# Moodlight20_ETP2.net
KiCad netlist of a schematic drawn in EAGLE
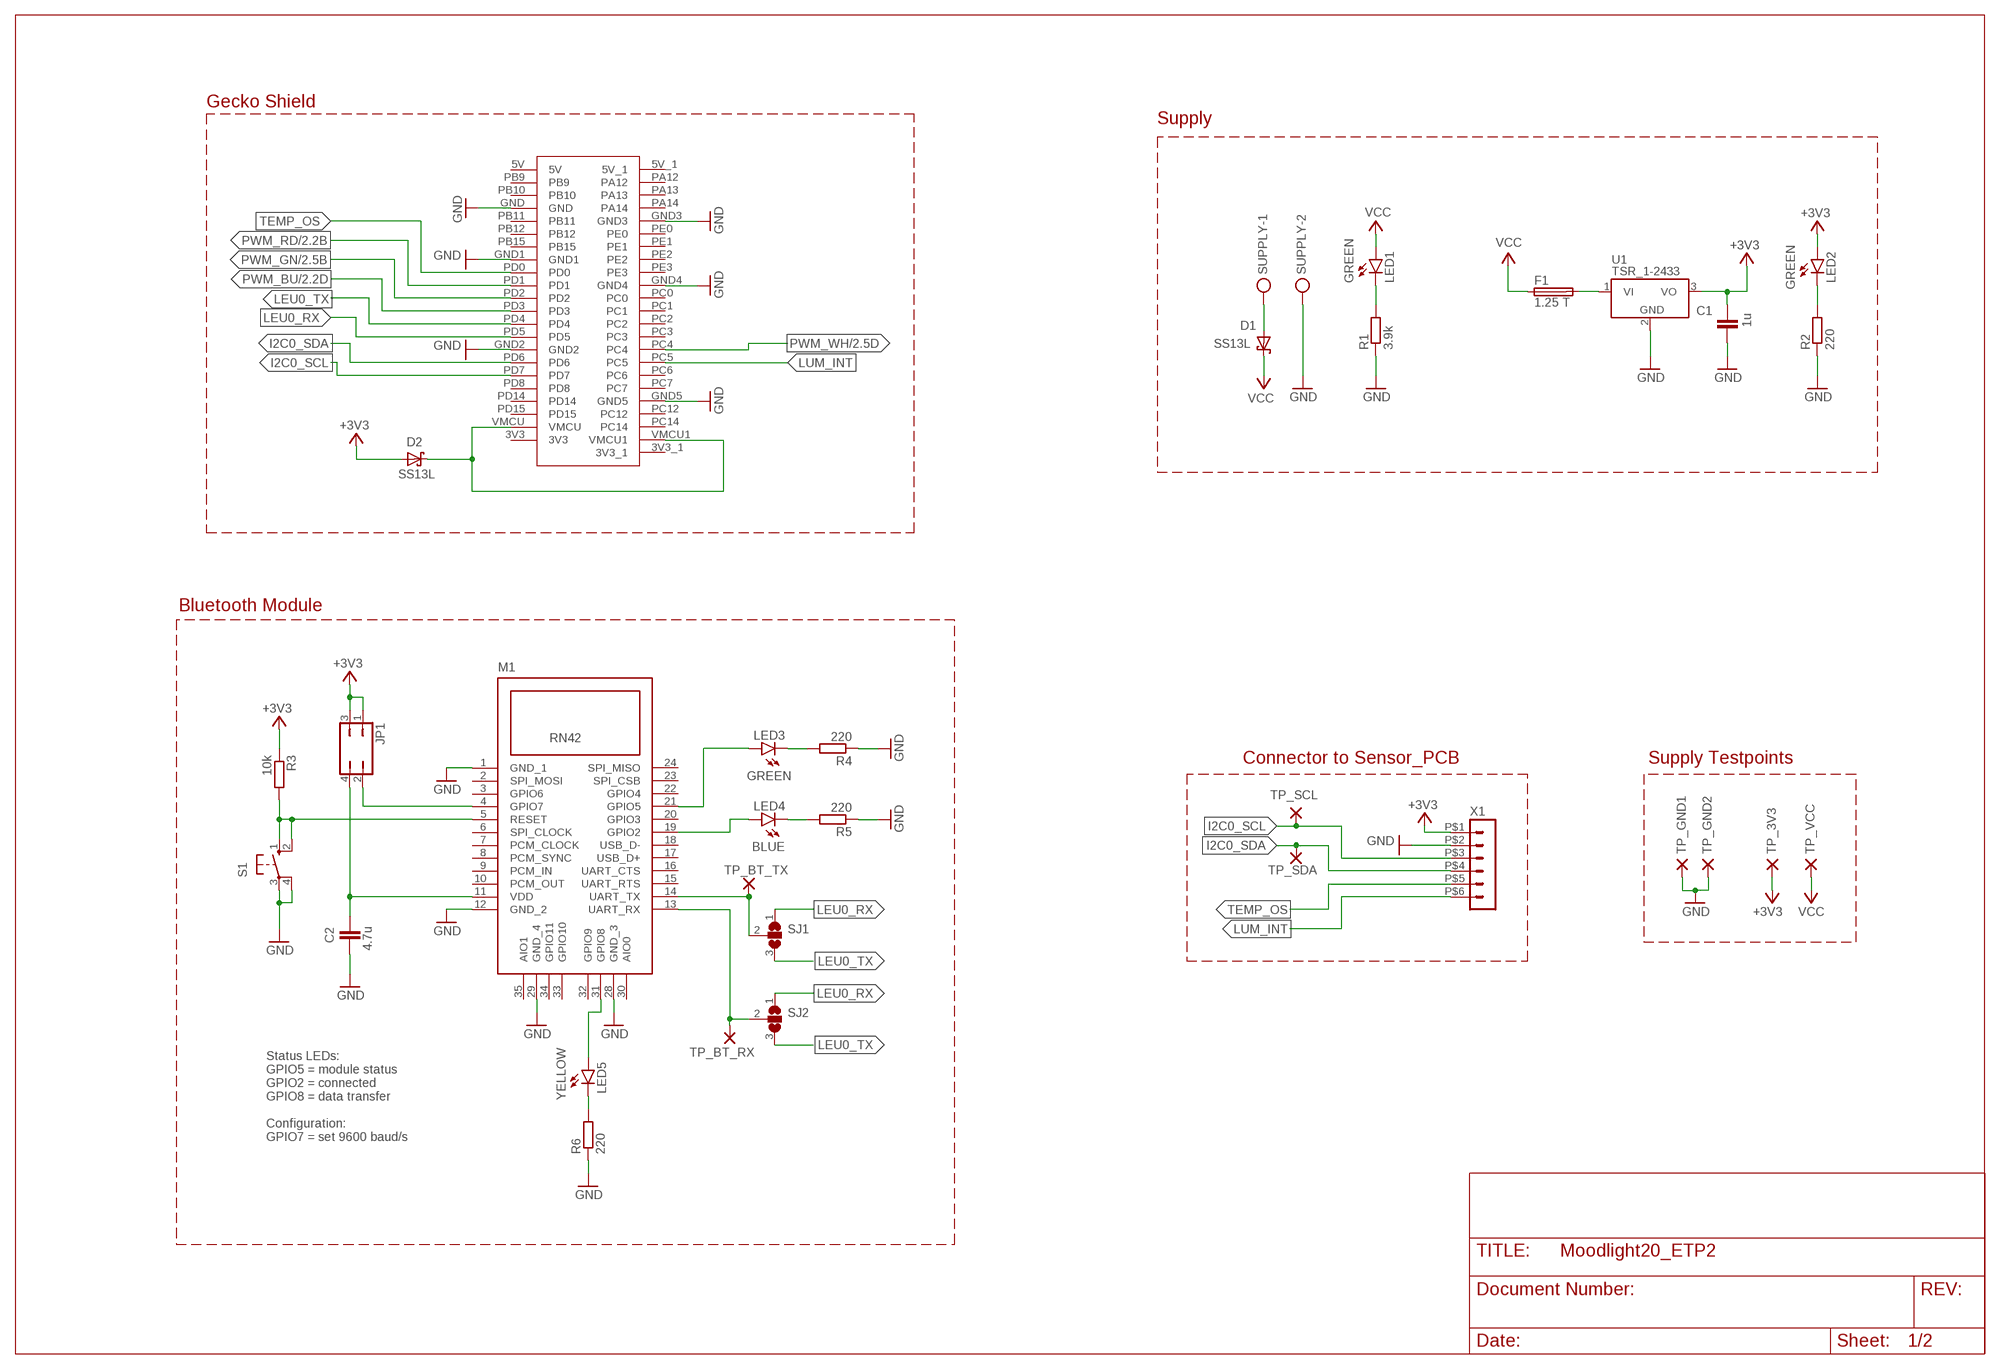
[diagram p0: schematic, sheet 1]
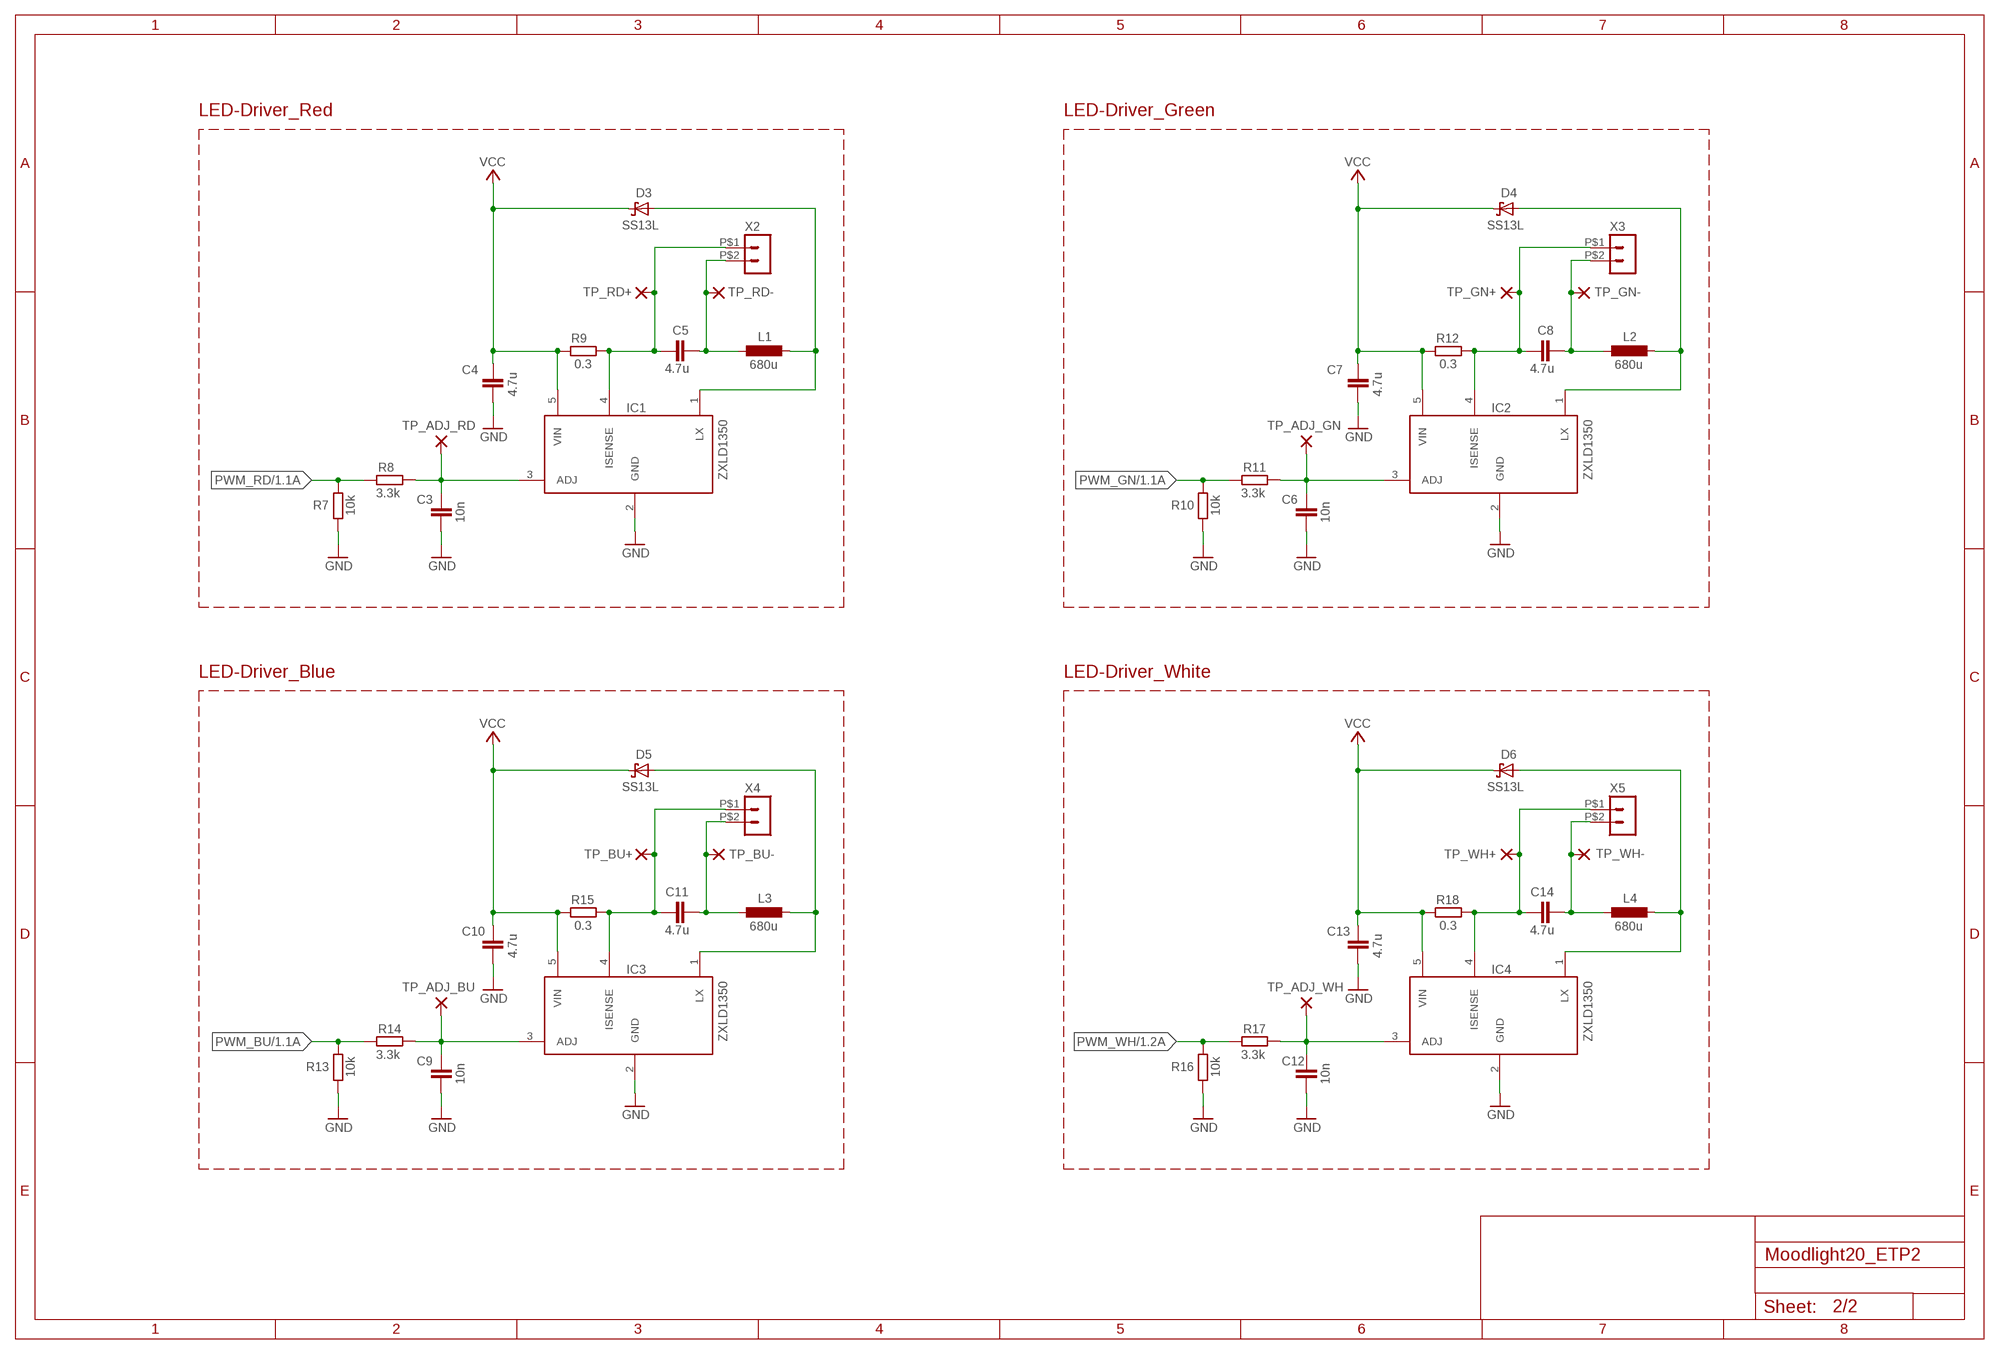
[diagram p1: schematic, sheet 2]

(export (version "E")
  (design (tool "Eeschema 10.0.6"))
  (components
    (comp (ref "C1")
      (value "1u")
      (footprint "eagle-import:C0805K")
      (libsource (lib "eagle-import") (part "C-EUC0805K"))
    )
    (comp (ref "C2")
      (value "4.7u")
      (footprint "eagle-import:C0805K")
      (libsource (lib "eagle-import") (part "C-EUC0805K"))
    )
    (comp (ref "D1")
      (value "SS13L")
      (footprint "eagle-import:SUB-SMA")
      (libsource (lib "eagle-import") (part "SS13L"))
    )
    (comp (ref "D2")
      (value "SS13L")
      (footprint "eagle-import:SUB-SMA")
      (libsource (lib "eagle-import") (part "SS13L"))
    )
    (comp (ref "F1")
      (value "1.25 T")
      (footprint "eagle-import:19560")
      (fields (field (name "MPN") "56000001009"))
      (libsource (lib "eagle-import") (part "19560"))
    )
    (comp (ref "GECKO")
      (value "GECKO_SHIELD")
      (footprint "eagle-import:GECKO_SHIELD")
      (libsource (lib "eagle-import") (part "GECKO_SHIELD"))
    )
    (comp (ref "JP1")
      (value "JP2Q")
      (footprint "eagle-import:JP2Q")
      (libsource (lib "eagle-import") (part "JP2Q"))
    )
    (comp (ref "LED1")
      (value "GREEN")
      (footprint "eagle-import:CHIP-LED0805")
      (fields (field (name "SPICEPREFIX") "L"))
      (libsource (lib "eagle-import") (part "LEDCHIP-LED0805"))
    )
    (comp (ref "LED2")
      (value "GREEN")
      (footprint "eagle-import:CHIP-LED0805")
      (fields (field (name "SPICEPREFIX") "L"))
      (libsource (lib "eagle-import") (part "LEDCHIP-LED0805"))
    )
    (comp (ref "LED3")
      (value "GREEN")
      (footprint "eagle-import:CHIP-LED0805")
      (fields (field (name "SPICEPREFIX") "L"))
      (libsource (lib "eagle-import") (part "LEDCHIP-LED0805"))
    )
    (comp (ref "LED4")
      (value "BLUE")
      (footprint "eagle-import:CHIP-LED0805")
      (fields (field (name "SPICEPREFIX") "L"))
      (libsource (lib "eagle-import") (part "LEDCHIP-LED0805"))
    )
    (comp (ref "LED5")
      (value "YELLOW")
      (footprint "eagle-import:CHIP-LED0805")
      (fields (field (name "SPICEPREFIX") "L"))
      (libsource (lib "eagle-import") (part "LEDCHIP-LED0805"))
    )
    (comp (ref "M1")
      (value "RN42_BLUETOOTH")
      (footprint "eagle-import:RN42_BLUETOOTH")
      (libsource (lib "eagle-import") (part "RN42_BLUETOOTH"))
    )
    (comp (ref "R1")
      (value "3.9k")
      (footprint "eagle-import:R0805")
      (libsource (lib "eagle-import") (part "R-EU_R0805"))
    )
    (comp (ref "R2")
      (value "220")
      (footprint "eagle-import:R0805")
      (libsource (lib "eagle-import") (part "R-EU_R0805"))
    )
    (comp (ref "R3")
      (value "10k")
      (footprint "eagle-import:R0805")
      (libsource (lib "eagle-import") (part "R-EU_R0805"))
    )
    (comp (ref "R4")
      (value "220")
      (footprint "eagle-import:R0805")
      (libsource (lib "eagle-import") (part "R-EU_R0805"))
    )
    (comp (ref "R5")
      (value "220")
      (footprint "eagle-import:R0805")
      (libsource (lib "eagle-import") (part "R-EU_R0805"))
    )
    (comp (ref "R6")
      (value "220")
      (footprint "eagle-import:R0805")
      (libsource (lib "eagle-import") (part "R-EU_R0805"))
    )
    (comp (ref "S1")
      (value "10-XX")
      (footprint "eagle-import:B3F-10XX")
      (fields (field (name "MPN") "B3F-1000"))
      (libsource (lib "eagle-import") (part "10-XX"))
    )
    (comp (ref "SJ1")
      (value "SJ2W")
      (footprint "eagle-import:SJ_2")
      (libsource (lib "eagle-import") (part "SJ2W"))
    )
    (comp (ref "SJ2")
      (value "SJ2W")
      (footprint "eagle-import:SJ_2")
      (libsource (lib "eagle-import") (part "SJ2W"))
    )
    (comp (ref "SUPPLY")
      (value "MKDSN1,5/2-5,08")
      (footprint "eagle-import:MKDSN1,5_2-5,08")
      (libsource (lib "eagle-import") (part "MKDSN1,5/2-5,08"))
    )
    (comp (ref "TP_3V3")
      (value "TESTPOINT")
      (footprint "eagle-import:3,2_1,6")
      (libsource (lib "eagle-import") (part "TESTPOINT"))
    )
    (comp (ref "TP_BT_RX")
      (value "TESTPOINT")
      (footprint "eagle-import:3,2_1,6")
      (libsource (lib "eagle-import") (part "TESTPOINT"))
    )
    (comp (ref "TP_BT_TX")
      (value "TESTPOINT")
      (footprint "eagle-import:3,2_1,6")
      (libsource (lib "eagle-import") (part "TESTPOINT"))
    )
    (comp (ref "TP_GND1")
      (value "TESTPOINT")
      (footprint "eagle-import:3,2_1,6")
      (libsource (lib "eagle-import") (part "TESTPOINT"))
    )
    (comp (ref "TP_GND2")
      (value "TESTPOINT")
      (footprint "eagle-import:3,2_1,6")
      (libsource (lib "eagle-import") (part "TESTPOINT"))
    )
    (comp (ref "TP_SCL")
      (value "TESTPOINT")
      (footprint "eagle-import:3,2_1,6")
      (libsource (lib "eagle-import") (part "TESTPOINT"))
    )
    (comp (ref "TP_SDA")
      (value "TESTPOINT")
      (footprint "eagle-import:3,2_1,6")
      (libsource (lib "eagle-import") (part "TESTPOINT"))
    )
    (comp (ref "TP_VCC")
      (value "TESTPOINT")
      (footprint "eagle-import:3,2_1,6")
      (libsource (lib "eagle-import") (part "TESTPOINT"))
    )
    (comp (ref "U1")
      (value "TSR_1-2433")
      (footprint "eagle-import:TSR-1")
      (libsource (lib "eagle-import") (part "TSR_1-2433"))
    )
    (comp (ref "X1")
      (value "HEADER_POS6_43045-0612")
      (footprint "eagle-import:43045-0612")
      (libsource (lib "eagle-import") (part "HEADER_POS6_?43045-0612"))
    )
    (comp (ref "C3")
      (value "10n")
      (footprint "eagle-import:C0805K")
      (libsource (lib "eagle-import") (part "C-EUC0805K"))
    )
    (comp (ref "C4")
      (value "4.7u")
      (footprint "eagle-import:C0805K")
      (libsource (lib "eagle-import") (part "C-EUC0805K"))
    )
    (comp (ref "C5")
      (value "4.7u")
      (footprint "eagle-import:C0805K")
      (libsource (lib "eagle-import") (part "C-EUC0805K"))
    )
    (comp (ref "C6")
      (value "10n")
      (footprint "eagle-import:C0805K")
      (libsource (lib "eagle-import") (part "C-EUC0805K"))
    )
    (comp (ref "C7")
      (value "4.7u")
      (footprint "eagle-import:C0805K")
      (libsource (lib "eagle-import") (part "C-EUC0805K"))
    )
    (comp (ref "C8")
      (value "4.7u")
      (footprint "eagle-import:C0805K")
      (libsource (lib "eagle-import") (part "C-EUC0805K"))
    )
    (comp (ref "C9")
      (value "10n")
      (footprint "eagle-import:C0805K")
      (libsource (lib "eagle-import") (part "C-EUC0805K"))
    )
    (comp (ref "C10")
      (value "4.7u")
      (footprint "eagle-import:C0805K")
      (libsource (lib "eagle-import") (part "C-EUC0805K"))
    )
    (comp (ref "C11")
      (value "4.7u")
      (footprint "eagle-import:C0805K")
      (libsource (lib "eagle-import") (part "C-EUC0805K"))
    )
    (comp (ref "C12")
      (value "10n")
      (footprint "eagle-import:C0805K")
      (libsource (lib "eagle-import") (part "C-EUC0805K"))
    )
    (comp (ref "C13")
      (value "4.7u")
      (footprint "eagle-import:C0805K")
      (libsource (lib "eagle-import") (part "C-EUC0805K"))
    )
    (comp (ref "C14")
      (value "4.7u")
      (footprint "eagle-import:C0805K")
      (libsource (lib "eagle-import") (part "C-EUC0805K"))
    )
    (comp (ref "D3")
      (value "SS13L")
      (footprint "eagle-import:SUB-SMA")
      (libsource (lib "eagle-import") (part "SS13L"))
    )
    (comp (ref "D4")
      (value "SS13L")
      (footprint "eagle-import:SUB-SMA")
      (libsource (lib "eagle-import") (part "SS13L"))
    )
    (comp (ref "D5")
      (value "SS13L")
      (footprint "eagle-import:SUB-SMA")
      (libsource (lib "eagle-import") (part "SS13L"))
    )
    (comp (ref "D6")
      (value "SS13L")
      (footprint "eagle-import:SUB-SMA")
      (libsource (lib "eagle-import") (part "SS13L"))
    )
    (comp (ref "IC1")
      (value "ZXLD1350")
      (footprint "eagle-import:TSOT23-5L")
      (libsource (lib "eagle-import") (part "ZXLD1350"))
    )
    (comp (ref "IC2")
      (value "ZXLD1350")
      (footprint "eagle-import:TSOT23-5L")
      (libsource (lib "eagle-import") (part "ZXLD1350"))
    )
    (comp (ref "IC3")
      (value "ZXLD1350")
      (footprint "eagle-import:TSOT23-5L")
      (libsource (lib "eagle-import") (part "ZXLD1350"))
    )
    (comp (ref "IC4")
      (value "ZXLD1350")
      (footprint "eagle-import:TSOT23-5L")
      (libsource (lib "eagle-import") (part "ZXLD1350"))
    )
    (comp (ref "L1")
      (value "680u")
      (footprint "eagle-import:POWER-CHOKE_WE-PD")
      (libsource (lib "eagle-import") (part "POWER-CHOKE_WE-PD"))
    )
    (comp (ref "L2")
      (value "680u")
      (footprint "eagle-import:POWER-CHOKE_WE-PD")
      (libsource (lib "eagle-import") (part "POWER-CHOKE_WE-PD"))
    )
    (comp (ref "L3")
      (value "680u")
      (footprint "eagle-import:POWER-CHOKE_WE-PD")
      (libsource (lib "eagle-import") (part "POWER-CHOKE_WE-PD"))
    )
    (comp (ref "L4")
      (value "680u")
      (footprint "eagle-import:POWER-CHOKE_WE-PD")
      (libsource (lib "eagle-import") (part "POWER-CHOKE_WE-PD"))
    )
    (comp (ref "R7")
      (value "10k")
      (footprint "eagle-import:R0805")
      (libsource (lib "eagle-import") (part "R-EU_R0805"))
    )
    (comp (ref "R8")
      (value "3.3k")
      (footprint "eagle-import:R0805")
      (libsource (lib "eagle-import") (part "R-EU_R0805"))
    )
    (comp (ref "R9")
      (value "0.3")
      (footprint "eagle-import:R1206")
      (libsource (lib "eagle-import") (part "R-EU_R1206"))
    )
    (comp (ref "R10")
      (value "10k")
      (footprint "eagle-import:R0805")
      (libsource (lib "eagle-import") (part "R-EU_R0805"))
    )
    (comp (ref "R11")
      (value "3.3k")
      (footprint "eagle-import:R0805")
      (libsource (lib "eagle-import") (part "R-EU_R0805"))
    )
    (comp (ref "R12")
      (value "0.3")
      (footprint "eagle-import:R1206")
      (libsource (lib "eagle-import") (part "R-EU_R1206"))
    )
    (comp (ref "R13")
      (value "10k")
      (footprint "eagle-import:R0805")
      (libsource (lib "eagle-import") (part "R-EU_R0805"))
    )
    (comp (ref "R14")
      (value "3.3k")
      (footprint "eagle-import:R0805")
      (libsource (lib "eagle-import") (part "R-EU_R0805"))
    )
    (comp (ref "R15")
      (value "0.3")
      (footprint "eagle-import:R1206")
      (libsource (lib "eagle-import") (part "R-EU_R1206"))
    )
    (comp (ref "R16")
      (value "10k")
      (footprint "eagle-import:R0805")
      (libsource (lib "eagle-import") (part "R-EU_R0805"))
    )
    (comp (ref "R17")
      (value "3.3k")
      (footprint "eagle-import:R0805")
      (libsource (lib "eagle-import") (part "R-EU_R0805"))
    )
    (comp (ref "R18")
      (value "0.3")
      (footprint "eagle-import:R1206")
      (libsource (lib "eagle-import") (part "R-EU_R1206"))
    )
    (comp (ref "TP_ADJ_BU")
      (value "TESTPOINT")
      (footprint "eagle-import:3,2_1,6")
      (libsource (lib "eagle-import") (part "TESTPOINT"))
    )
    (comp (ref "TP_ADJ_GN")
      (value "TESTPOINT")
      (footprint "eagle-import:3,2_1,6")
      (libsource (lib "eagle-import") (part "TESTPOINT"))
    )
    (comp (ref "TP_ADJ_RD")
      (value "TESTPOINT")
      (footprint "eagle-import:3,2_1,6")
      (libsource (lib "eagle-import") (part "TESTPOINT"))
    )
    (comp (ref "TP_ADJ_WH")
      (value "TESTPOINT")
      (footprint "eagle-import:3,2_1,6")
      (libsource (lib "eagle-import") (part "TESTPOINT"))
    )
    (comp (ref "TP_BU+")
      (value "TESTPOINT")
      (footprint "eagle-import:3,2_1,6")
      (libsource (lib "eagle-import") (part "TESTPOINT"))
    )
    (comp (ref "TP_BU-")
      (value "TESTPOINT")
      (footprint "eagle-import:3,2_1,6")
      (libsource (lib "eagle-import") (part "TESTPOINT"))
    )
    (comp (ref "TP_GN+")
      (value "TESTPOINT")
      (footprint "eagle-import:3,2_1,6")
      (libsource (lib "eagle-import") (part "TESTPOINT"))
    )
    (comp (ref "TP_GN-")
      (value "TESTPOINT")
      (footprint "eagle-import:3,2_1,6")
      (libsource (lib "eagle-import") (part "TESTPOINT"))
    )
    (comp (ref "TP_RD+")
      (value "TESTPOINT")
      (footprint "eagle-import:3,2_1,6")
      (libsource (lib "eagle-import") (part "TESTPOINT"))
    )
    (comp (ref "TP_RD-")
      (value "TESTPOINT")
      (footprint "eagle-import:3,2_1,6")
      (libsource (lib "eagle-import") (part "TESTPOINT"))
    )
    (comp (ref "TP_WH+")
      (value "TESTPOINT")
      (footprint "eagle-import:3,2_1,6")
      (libsource (lib "eagle-import") (part "TESTPOINT"))
    )
    (comp (ref "TP_WH-")
      (value "TESTPOINT")
      (footprint "eagle-import:3,2_1,6")
      (libsource (lib "eagle-import") (part "TESTPOINT"))
    )
    (comp (ref "X2")
      (value "HEADER_POS2_43650-0215")
      (footprint "eagle-import:43650-0215")
      (libsource (lib "eagle-import") (part "HEADER_POS2_?43650-0215"))
    )
    (comp (ref "X3")
      (value "HEADER_POS2_43650-0215")
      (footprint "eagle-import:43650-0215")
      (libsource (lib "eagle-import") (part "HEADER_POS2_?43650-0215"))
    )
    (comp (ref "X4")
      (value "HEADER_POS2_43650-0215")
      (footprint "eagle-import:43650-0215")
      (libsource (lib "eagle-import") (part "HEADER_POS2_?43650-0215"))
    )
    (comp (ref "X5")
      (value "HEADER_POS2_43650-0215")
      (footprint "eagle-import:43650-0215")
      (libsource (lib "eagle-import") (part "HEADER_POS2_?43650-0215"))
    )
  )
  (nets
    (net (code "1") (name "+3V3") (class "Default")
      (node (ref "C1") (pin "1") (pinfunction "1_1") (pintype "passive"))
      (node (ref "D2") (pin "A") (pinfunction "A_A") (pintype "passive"))
      (node (ref "JP1") (pin "1") (pinfunction "1_1") (pintype "passive"))
      (node (ref "JP1") (pin "3") (pinfunction "3_3") (pintype "passive"))
      (node (ref "LED2") (pin "A") (pinfunction "A_A") (pintype "passive"))
      (node (ref "R3") (pin "1") (pinfunction "1_1") (pintype "passive"))
      (node (ref "TP_3V3") (pin "1") (pinfunction "P_1") (pintype "passive"))
      (node (ref "U1") (pin "3") (pinfunction "VO_3") (pintype "power_in"))
      (node (ref "X1") (pin "P$1") (pinfunction "1_P$1") (pintype "passive"))
    )
    (net (code "2") (name "GND") (class "Default")
      (node (ref "C1") (pin "2") (pinfunction "2_2") (pintype "passive"))
      (node (ref "C10") (pin "2") (pinfunction "2_2") (pintype "passive"))
      (node (ref "C12") (pin "2") (pinfunction "2_2") (pintype "passive"))
      (node (ref "C13") (pin "2") (pinfunction "2_2") (pintype "passive"))
      (node (ref "C2") (pin "1") (pinfunction "1_1") (pintype "passive"))
      (node (ref "C3") (pin "2") (pinfunction "2_2") (pintype "passive"))
      (node (ref "C4") (pin "2") (pinfunction "2_2") (pintype "passive"))
      (node (ref "C6") (pin "2") (pinfunction "2_2") (pintype "passive"))
      (node (ref "C7") (pin "2") (pinfunction "2_2") (pintype "passive"))
      (node (ref "C9") (pin "2") (pinfunction "2_2") (pintype "passive"))
      (node (ref "GECKO") (pin "GND") (pinfunction "GND_GND") (pintype "bidirectional"))
      (node (ref "GECKO") (pin "GND1") (pinfunction "GND1_GND1") (pintype "bidirectional"))
      (node (ref "GECKO") (pin "GND2") (pinfunction "GND2_GND2") (pintype "bidirectional"))
      (node (ref "GECKO") (pin "GND3") (pinfunction "GND3_GND3") (pintype "bidirectional"))
      (node (ref "GECKO") (pin "GND4") (pinfunction "GND4_GND4") (pintype "bidirectional"))
      (node (ref "GECKO") (pin "GND5") (pinfunction "GND5_GND5") (pintype "bidirectional"))
      (node (ref "IC1") (pin "2") (pinfunction "GND_2") (pintype "bidirectional"))
      (node (ref "IC2") (pin "2") (pinfunction "GND_2") (pintype "bidirectional"))
      (node (ref "IC3") (pin "2") (pinfunction "GND_2") (pintype "bidirectional"))
      (node (ref "IC4") (pin "2") (pinfunction "GND_2") (pintype "bidirectional"))
      (node (ref "M1") (pin "1") (pinfunction "GND_1_1") (pintype "bidirectional"))
      (node (ref "M1") (pin "12") (pinfunction "GND_2_12") (pintype "bidirectional"))
      (node (ref "M1") (pin "28") (pinfunction "GND_3_28") (pintype "bidirectional"))
      (node (ref "M1") (pin "29") (pinfunction "GND_4_29") (pintype "bidirectional"))
      (node (ref "R1") (pin "1") (pinfunction "1_1") (pintype "passive"))
      (node (ref "R10") (pin "1") (pinfunction "1_1") (pintype "passive"))
      (node (ref "R13") (pin "1") (pinfunction "1_1") (pintype "passive"))
      (node (ref "R16") (pin "1") (pinfunction "1_1") (pintype "passive"))
      (node (ref "R2") (pin "1") (pinfunction "1_1") (pintype "passive"))
      (node (ref "R4") (pin "1") (pinfunction "1_1") (pintype "passive"))
      (node (ref "R5") (pin "1") (pinfunction "1_1") (pintype "passive"))
      (node (ref "R6") (pin "1") (pinfunction "1_1") (pintype "passive"))
      (node (ref "R7") (pin "1") (pinfunction "1_1") (pintype "passive"))
      (node (ref "S1") (pin "3") (pinfunction "P_3") (pintype "passive"))
      (node (ref "S1") (pin "4") (pinfunction "P1_4") (pintype "passive"))
      (node (ref "SUPPLY") (pin "2") (pinfunction "KL_2") (pintype "passive"))
      (node (ref "TP_GND1") (pin "1") (pinfunction "P_1") (pintype "passive"))
      (node (ref "TP_GND2") (pin "1") (pinfunction "P_1") (pintype "passive"))
      (node (ref "U1") (pin "2") (pinfunction "GND_2") (pintype "power_in"))
      (node (ref "X1") (pin "P$2") (pinfunction "2_P$2") (pintype "passive"))
    )
    (net (code "3") (name "I2C0_SCL") (class "Default")
      (node (ref "GECKO") (pin "PD7") (pinfunction "PD7_PD7") (pintype "bidirectional"))
      (node (ref "TP_SCL") (pin "1") (pinfunction "P_1") (pintype "passive"))
      (node (ref "X1") (pin "P$3") (pinfunction "3_P$3") (pintype "passive"))
    )
    (net (code "4") (name "I2C0_SDA") (class "Default")
      (node (ref "GECKO") (pin "PD6") (pinfunction "PD6_PD6") (pintype "bidirectional"))
      (node (ref "TP_SDA") (pin "1") (pinfunction "P_1") (pintype "passive"))
      (node (ref "X1") (pin "P$4") (pinfunction "4_P$4") (pintype "passive"))
    )
    (net (code "5") (name "LEU0_RX") (class "Default")
      (node (ref "GECKO") (pin "PD5") (pinfunction "PD5_PD5") (pintype "bidirectional"))
      (node (ref "SJ1") (pin "1") (pinfunction "1_1") (pintype "passive"))
      (node (ref "SJ2") (pin "1") (pinfunction "1_1") (pintype "passive"))
    )
    (net (code "6") (name "LEU0_TX") (class "Default")
      (node (ref "GECKO") (pin "PD4") (pinfunction "PD4_PD4") (pintype "bidirectional"))
      (node (ref "SJ1") (pin "3") (pinfunction "3_3") (pintype "passive"))
      (node (ref "SJ2") (pin "3") (pinfunction "3_3") (pintype "passive"))
    )
    (net (code "7") (name "LUM_INT") (class "Default")
      (node (ref "GECKO") (pin "PC5") (pinfunction "PC5_PC5") (pintype "bidirectional"))
      (node (ref "X1") (pin "P$6") (pinfunction "6_P$6") (pintype "passive"))
    )
    (net (code "8") (name "Net-(D2-PadC)") (class "Default")
      (node (ref "D2") (pin "C") (pinfunction "C_C") (pintype "passive"))
      (node (ref "GECKO") (pin "VMCU") (pinfunction "VMCU_VMCU") (pintype "bidirectional"))
      (node (ref "GECKO") (pin "VMCU1") (pinfunction "VMCU1_VMCU1") (pintype "bidirectional"))
    )
    (net (code "9") (name "Net-(IC1-ADJ)") (class "Default")
      (node (ref "C3") (pin "1") (pinfunction "1_1") (pintype "passive"))
      (node (ref "IC1") (pin "3") (pinfunction "ADJ_3") (pintype "bidirectional"))
      (node (ref "R8") (pin "1") (pinfunction "1_1") (pintype "passive"))
      (node (ref "TP_ADJ_RD") (pin "1") (pinfunction "P_1") (pintype "passive"))
    )
    (net (code "10") (name "Net-(IC1-ISENSE)") (class "Default")
      (node (ref "C5") (pin "1") (pinfunction "1_1") (pintype "passive"))
      (node (ref "IC1") (pin "4") (pinfunction "ISENSE_4") (pintype "bidirectional"))
      (node (ref "R9") (pin "2") (pinfunction "2_2") (pintype "passive"))
      (node (ref "TP_RD+") (pin "1") (pinfunction "P_1") (pintype "passive"))
      (node (ref "X2") (pin "P$1") (pinfunction "1_P$1") (pintype "passive"))
    )
    (net (code "11") (name "Net-(IC1-LX)") (class "Default")
      (node (ref "D3") (pin "A") (pinfunction "A_A") (pintype "passive"))
      (node (ref "IC1") (pin "1") (pinfunction "LX_1") (pintype "bidirectional"))
      (node (ref "L1") (pin "2") (pinfunction "2_2") (pintype "passive"))
    )
    (net (code "12") (name "Net-(IC2-ADJ)") (class "Default")
      (node (ref "C6") (pin "1") (pinfunction "1_1") (pintype "passive"))
      (node (ref "IC2") (pin "3") (pinfunction "ADJ_3") (pintype "bidirectional"))
      (node (ref "R11") (pin "1") (pinfunction "1_1") (pintype "passive"))
      (node (ref "TP_ADJ_GN") (pin "1") (pinfunction "P_1") (pintype "passive"))
    )
    (net (code "13") (name "Net-(IC2-ISENSE)") (class "Default")
      (node (ref "C8") (pin "1") (pinfunction "1_1") (pintype "passive"))
      (node (ref "IC2") (pin "4") (pinfunction "ISENSE_4") (pintype "bidirectional"))
      (node (ref "R12") (pin "2") (pinfunction "2_2") (pintype "passive"))
      (node (ref "TP_GN+") (pin "1") (pinfunction "P_1") (pintype "passive"))
      (node (ref "X3") (pin "P$1") (pinfunction "1_P$1") (pintype "passive"))
    )
    (net (code "14") (name "Net-(IC2-LX)") (class "Default")
      (node (ref "D4") (pin "A") (pinfunction "A_A") (pintype "passive"))
      (node (ref "IC2") (pin "1") (pinfunction "LX_1") (pintype "bidirectional"))
      (node (ref "L2") (pin "2") (pinfunction "2_2") (pintype "passive"))
    )
    (net (code "15") (name "Net-(IC3-ADJ)") (class "Default")
      (node (ref "C9") (pin "1") (pinfunction "1_1") (pintype "passive"))
      (node (ref "IC3") (pin "3") (pinfunction "ADJ_3") (pintype "bidirectional"))
      (node (ref "R14") (pin "1") (pinfunction "1_1") (pintype "passive"))
      (node (ref "TP_ADJ_BU") (pin "1") (pinfunction "P_1") (pintype "passive"))
    )
    (net (code "16") (name "Net-(IC3-ISENSE)") (class "Default")
      (node (ref "C11") (pin "1") (pinfunction "1_1") (pintype "passive"))
      (node (ref "IC3") (pin "4") (pinfunction "ISENSE_4") (pintype "bidirectional"))
      (node (ref "R15") (pin "2") (pinfunction "2_2") (pintype "passive"))
      (node (ref "TP_BU+") (pin "1") (pinfunction "P_1") (pintype "passive"))
      (node (ref "X4") (pin "P$1") (pinfunction "1_P$1") (pintype "passive"))
    )
    (net (code "17") (name "Net-(IC3-LX)") (class "Default")
      (node (ref "D5") (pin "A") (pinfunction "A_A") (pintype "passive"))
      (node (ref "IC3") (pin "1") (pinfunction "LX_1") (pintype "bidirectional"))
      (node (ref "L3") (pin "2") (pinfunction "2_2") (pintype "passive"))
    )
    (net (code "18") (name "Net-(IC4-ADJ)") (class "Default")
      (node (ref "C12") (pin "1") (pinfunction "1_1") (pintype "passive"))
      (node (ref "IC4") (pin "3") (pinfunction "ADJ_3") (pintype "bidirectional"))
      (node (ref "R17") (pin "1") (pinfunction "1_1") (pintype "passive"))
      (node (ref "TP_ADJ_WH") (pin "1") (pinfunction "P_1") (pintype "passive"))
    )
    (net (code "19") (name "Net-(IC4-ISENSE)") (class "Default")
      (node (ref "C14") (pin "1") (pinfunction "1_1") (pintype "passive"))
      (node (ref "IC4") (pin "4") (pinfunction "ISENSE_4") (pintype "bidirectional"))
      (node (ref "R18") (pin "2") (pinfunction "2_2") (pintype "passive"))
      (node (ref "TP_WH+") (pin "1") (pinfunction "P_1") (pintype "passive"))
      (node (ref "X5") (pin "P$1") (pinfunction "1_P$1") (pintype "passive"))
    )
    (net (code "20") (name "Net-(IC4-LX)") (class "Default")
      (node (ref "D6") (pin "A") (pinfunction "A_A") (pintype "passive"))
      (node (ref "IC4") (pin "1") (pinfunction "LX_1") (pintype "bidirectional"))
      (node (ref "L4") (pin "2") (pinfunction "2_2") (pintype "passive"))
    )
    (net (code "21") (name "Net-(LED1-PadC)") (class "Default")
      (node (ref "LED1") (pin "C") (pinfunction "C_C") (pintype "passive"))
      (node (ref "R1") (pin "2") (pinfunction "2_2") (pintype "passive"))
    )
    (net (code "22") (name "Net-(LED2-PadC)") (class "Default")
      (node (ref "LED2") (pin "C") (pinfunction "C_C") (pintype "passive"))
      (node (ref "R2") (pin "2") (pinfunction "2_2") (pintype "passive"))
    )
    (net (code "23") (name "Net-(LED3-PadC)") (class "Default")
      (node (ref "LED3") (pin "C") (pinfunction "C_C") (pintype "passive"))
      (node (ref "R4") (pin "2") (pinfunction "2_2") (pintype "passive"))
    )
    (net (code "24") (name "Net-(LED4-PadC)") (class "Default")
      (node (ref "LED4") (pin "C") (pinfunction "C_C") (pintype "passive"))
      (node (ref "R5") (pin "2") (pinfunction "2_2") (pintype "passive"))
    )
    (net (code "25") (name "Net-(LED5-PadC)") (class "Default")
      (node (ref "LED5") (pin "C") (pinfunction "C_C") (pintype "passive"))
      (node (ref "R6") (pin "2") (pinfunction "2_2") (pintype "passive"))
    )
    (net (code "26") (name "Net-(M1-GPIO2)") (class "Default")
      (node (ref "LED4") (pin "A") (pinfunction "A_A") (pintype "passive"))
      (node (ref "M1") (pin "19") (pinfunction "GPIO2_19") (pintype "bidirectional"))
    )
    (net (code "27") (name "Net-(M1-GPIO5)") (class "Default")
      (node (ref "LED3") (pin "A") (pinfunction "A_A") (pintype "passive"))
      (node (ref "M1") (pin "21") (pinfunction "GPIO5_21") (pintype "bidirectional"))
    )
    (net (code "28") (name "Net-(M1-GPIO7)") (class "Default")
      (node (ref "JP1") (pin "2") (pinfunction "2_2") (pintype "passive"))
      (node (ref "M1") (pin "4") (pinfunction "GPIO7_4") (pintype "bidirectional"))
    )
    (net (code "29") (name "Net-(M1-GPIO8)") (class "Default")
      (node (ref "LED5") (pin "A") (pinfunction "A_A") (pintype "passive"))
      (node (ref "M1") (pin "31") (pinfunction "GPIO8_31") (pintype "bidirectional"))
    )
    (net (code "30") (name "Net-(M1-RESET)") (class "Default")
      (node (ref "M1") (pin "5") (pinfunction "RESET_5") (pintype "bidirectional"))
      (node (ref "R3") (pin "2") (pinfunction "2_2") (pintype "passive"))
      (node (ref "S1") (pin "1") (pinfunction "S_1") (pintype "passive"))
      (node (ref "S1") (pin "2") (pinfunction "S1_2") (pintype "passive"))
    )
    (net (code "31") (name "Net-(M1-UART_RX)") (class "Default")
      (node (ref "M1") (pin "13") (pinfunction "UART_RX_13") (pintype "bidirectional"))
      (node (ref "SJ2") (pin "2") (pinfunction "2_2") (pintype "passive"))
      (node (ref "TP_BT_RX") (pin "1") (pinfunction "P_1") (pintype "passive"))
    )
    (net (code "32") (name "Net-(M1-UART_TX)") (class "Default")
      (node (ref "M1") (pin "14") (pinfunction "UART_TX_14") (pintype "bidirectional"))
      (node (ref "SJ1") (pin "2") (pinfunction "2_2") (pintype "passive"))
      (node (ref "TP_BT_TX") (pin "1") (pinfunction "P_1") (pintype "passive"))
    )
    (net (code "33") (name "Net-(M1-VDD)") (class "Default")
      (node (ref "C2") (pin "2") (pinfunction "2_2") (pintype "passive"))
      (node (ref "JP1") (pin "4") (pinfunction "4_4") (pintype "passive"))
      (node (ref "M1") (pin "11") (pinfunction "VDD_11") (pintype "bidirectional"))
    )
    (net (code "34") (name "Net-(SUPPLYA-KL)") (class "Default")
      (node (ref "D1") (pin "A") (pinfunction "A_A") (pintype "passive"))
      (node (ref "SUPPLY") (pin "1") (pinfunction "KL_1") (pintype "passive"))
    )
    (net (code "35") (name "Net-(TP_BU--P)") (class "Default")
      (node (ref "C11") (pin "2") (pinfunction "2_2") (pintype "passive"))
      (node (ref "L3") (pin "1") (pinfunction "1_1") (pintype "passive"))
      (node (ref "TP_BU-") (pin "1") (pinfunction "P_1") (pintype "passive"))
      (node (ref "X4") (pin "P$2") (pinfunction "2_P$2") (pintype "passive"))
    )
    (net (code "36") (name "Net-(TP_GN--P)") (class "Default")
      (node (ref "C8") (pin "2") (pinfunction "2_2") (pintype "passive"))
      (node (ref "L2") (pin "1") (pinfunction "1_1") (pintype "passive"))
      (node (ref "TP_GN-") (pin "1") (pinfunction "P_1") (pintype "passive"))
      (node (ref "X3") (pin "P$2") (pinfunction "2_P$2") (pintype "passive"))
    )
    (net (code "37") (name "Net-(TP_RD--P)") (class "Default")
      (node (ref "C5") (pin "2") (pinfunction "2_2") (pintype "passive"))
      (node (ref "L1") (pin "1") (pinfunction "1_1") (pintype "passive"))
      (node (ref "TP_RD-") (pin "1") (pinfunction "P_1") (pintype "passive"))
      (node (ref "X2") (pin "P$2") (pinfunction "2_P$2") (pintype "passive"))
    )
    (net (code "38") (name "Net-(TP_WH--P)") (class "Default")
      (node (ref "C14") (pin "2") (pinfunction "2_2") (pintype "passive"))
      (node (ref "L4") (pin "1") (pinfunction "1_1") (pintype "passive"))
      (node (ref "TP_WH-") (pin "1") (pinfunction "P_1") (pintype "passive"))
      (node (ref "X5") (pin "P$2") (pinfunction "2_P$2") (pintype "passive"))
    )
    (net (code "39") (name "Net-(U1-VI)") (class "Default")
      (node (ref "F1") (pin "2") (pinfunction "2_2") (pintype "passive"))
      (node (ref "U1") (pin "1") (pinfunction "VI_1") (pintype "power_in"))
    )
    (net (code "40") (name "PWM_BU") (class "Default")
      (node (ref "GECKO") (pin "PD3") (pinfunction "PD3_PD3") (pintype "bidirectional"))
      (node (ref "R13") (pin "2") (pinfunction "2_2") (pintype "passive"))
      (node (ref "R14") (pin "2") (pinfunction "2_2") (pintype "passive"))
    )
    (net (code "41") (name "PWM_GN") (class "Default")
      (node (ref "GECKO") (pin "PD2") (pinfunction "PD2_PD2") (pintype "bidirectional"))
      (node (ref "R10") (pin "2") (pinfunction "2_2") (pintype "passive"))
      (node (ref "R11") (pin "2") (pinfunction "2_2") (pintype "passive"))
    )
    (net (code "42") (name "PWM_RD") (class "Default")
      (node (ref "GECKO") (pin "PD1") (pinfunction "PD1_PD1") (pintype "bidirectional"))
      (node (ref "R7") (pin "2") (pinfunction "2_2") (pintype "passive"))
      (node (ref "R8") (pin "2") (pinfunction "2_2") (pintype "passive"))
    )
    (net (code "43") (name "PWM_WH") (class "Default")
      (node (ref "GECKO") (pin "PC4") (pinfunction "PC4_PC4") (pintype "bidirectional"))
      (node (ref "R16") (pin "2") (pinfunction "2_2") (pintype "passive"))
      (node (ref "R17") (pin "2") (pinfunction "2_2") (pintype "passive"))
    )
    (net (code "44") (name "TEMP_OS") (class "Default")
      (node (ref "GECKO") (pin "PD0") (pinfunction "PD0_PD0") (pintype "bidirectional"))
      (node (ref "X1") (pin "P$5") (pinfunction "5_P$5") (pintype "passive"))
    )
    (net (code "45") (name "VCC") (class "Default")
      (node (ref "C10") (pin "1") (pinfunction "1_1") (pintype "passive"))
      (node (ref "C13") (pin "1") (pinfunction "1_1") (pintype "passive"))
      (node (ref "C4") (pin "1") (pinfunction "1_1") (pintype "passive"))
      (node (ref "C7") (pin "1") (pinfunction "1_1") (pintype "passive"))
      (node (ref "D1") (pin "C") (pinfunction "C_C") (pintype "passive"))
      (node (ref "D3") (pin "C") (pinfunction "C_C") (pintype "passive"))
      (node (ref "D4") (pin "C") (pinfunction "C_C") (pintype "passive"))
      (node (ref "D5") (pin "C") (pinfunction "C_C") (pintype "passive"))
      (node (ref "D6") (pin "C") (pinfunction "C_C") (pintype "passive"))
      (node (ref "F1") (pin "1") (pinfunction "1_1") (pintype "passive"))
      (node (ref "IC1") (pin "5") (pinfunction "VIN_5") (pintype "bidirectional"))
      (node (ref "IC2") (pin "5") (pinfunction "VIN_5") (pintype "bidirectional"))
      (node (ref "IC3") (pin "5") (pinfunction "VIN_5") (pintype "bidirectional"))
      (node (ref "IC4") (pin "5") (pinfunction "VIN_5") (pintype "bidirectional"))
      (node (ref "LED1") (pin "A") (pinfunction "A_A") (pintype "passive"))
      (node (ref "R12") (pin "1") (pinfunction "1_1") (pintype "passive"))
      (node (ref "R15") (pin "1") (pinfunction "1_1") (pintype "passive"))
      (node (ref "R18") (pin "1") (pinfunction "1_1") (pintype "passive"))
      (node (ref "R9") (pin "1") (pinfunction "1_1") (pintype "passive"))
      (node (ref "TP_VCC") (pin "1") (pinfunction "P_1") (pintype "passive"))
    )
    (net (code "46") (name "unconnected-(GECKO-Pad3V3)") (class "Default")
      (node (ref "GECKO") (pin "3V3") (pinfunction "3V3_3V3") (pintype "bidirectional"))
    )
    (net (code "47") (name "unconnected-(GECKO-Pad3V3_1)") (class "Default")
      (node (ref "GECKO") (pin "3V3_1") (pinfunction "3V3_1_3V3_1") (pintype "bidirectional"))
    )
    (net (code "48") (name "unconnected-(GECKO-Pad5V)") (class "Default")
      (node (ref "GECKO") (pin "5V") (pinfunction "5V_5V") (pintype "bidirectional"))
    )
    (net (code "49") (name "unconnected-(GECKO-Pad5V_1)") (class "Default")
      (node (ref "GECKO") (pin "5V_1") (pinfunction "5V_1_5V_1") (pintype "bidirectional"))
    )
    (net (code "50") (name "unconnected-(GECKO-PadPA12)") (class "Default")
      (node (ref "GECKO") (pin "PA12") (pinfunction "PA12_PA12") (pintype "bidirectional"))
    )
    (net (code "51") (name "unconnected-(GECKO-PadPA13)") (class "Default")
      (node (ref "GECKO") (pin "PA13") (pinfunction "PA13_PA13") (pintype "bidirectional"))
    )
    (net (code "52") (name "unconnected-(GECKO-PadPA14)") (class "Default")
      (node (ref "GECKO") (pin "PA14") (pinfunction "PA14_PA14") (pintype "bidirectional"))
    )
    (net (code "53") (name "unconnected-(GECKO-PadPB9)") (class "Default")
      (node (ref "GECKO") (pin "PB9") (pinfunction "PB9_PB9") (pintype "bidirectional"))
    )
    (net (code "54") (name "unconnected-(GECKO-PadPB10)") (class "Default")
      (node (ref "GECKO") (pin "PB10") (pinfunction "PB10_PB10") (pintype "bidirectional"))
    )
    (net (code "55") (name "unconnected-(GECKO-PadPB11)") (class "Default")
      (node (ref "GECKO") (pin "PB11") (pinfunction "PB11_PB11") (pintype "bidirectional"))
    )
    (net (code "56") (name "unconnected-(GECKO-PadPB12)") (class "Default")
      (node (ref "GECKO") (pin "PB12") (pinfunction "PB12_PB12") (pintype "bidirectional"))
    )
    (net (code "57") (name "unconnected-(GECKO-PadPB15)") (class "Default")
      (node (ref "GECKO") (pin "PB15") (pinfunction "PB15_PB15") (pintype "bidirectional"))
    )
    (net (code "58") (name "unconnected-(GECKO-PadPC0)") (class "Default")
      (node (ref "GECKO") (pin "PC0") (pinfunction "PC0_PC0") (pintype "bidirectional"))
    )
    (net (code "59") (name "unconnected-(GECKO-PadPC1)") (class "Default")
      (node (ref "GECKO") (pin "PC1") (pinfunction "PC1_PC1") (pintype "bidirectional"))
    )
    (net (code "60") (name "unconnected-(GECKO-PadPC2)") (class "Default")
      (node (ref "GECKO") (pin "PC2") (pinfunction "PC2_PC2") (pintype "bidirectional"))
    )
    (net (code "61") (name "unconnected-(GECKO-PadPC3)") (class "Default")
      (node (ref "GECKO") (pin "PC3") (pinfunction "PC3_PC3") (pintype "bidirectional"))
    )
    (net (code "62") (name "unconnected-(GECKO-PadPC6)") (class "Default")
      (node (ref "GECKO") (pin "PC6") (pinfunction "PC6_PC6") (pintype "bidirectional"))
    )
    (net (code "63") (name "unconnected-(GECKO-PadPC7)") (class "Default")
      (node (ref "GECKO") (pin "PC7") (pinfunction "PC7_PC7") (pintype "bidirectional"))
    )
    (net (code "64") (name "unconnected-(GECKO-PadPC12)") (class "Default")
      (node (ref "GECKO") (pin "PC12") (pinfunction "PC12_PC12") (pintype "bidirectional"))
    )
    (net (code "65") (name "unconnected-(GECKO-PadPC14)") (class "Default")
      (node (ref "GECKO") (pin "PC14") (pinfunction "PC14_PC14") (pintype "bidirectional"))
    )
    (net (code "66") (name "unconnected-(GECKO-PadPD8)") (class "Default")
      (node (ref "GECKO") (pin "PD8") (pinfunction "PD8_PD8") (pintype "bidirectional"))
    )
    (net (code "67") (name "unconnected-(GECKO-PadPD14)") (class "Default")
      (node (ref "GECKO") (pin "PD14") (pinfunction "PD14_PD14") (pintype "bidirectional"))
    )
    (net (code "68") (name "unconnected-(GECKO-PadPD15)") (class "Default")
      (node (ref "GECKO") (pin "PD15") (pinfunction "PD15_PD15") (pintype "bidirectional"))
    )
    (net (code "69") (name "unconnected-(GECKO-PadPE0)") (class "Default")
      (node (ref "GECKO") (pin "PE0") (pinfunction "PE0_PE0") (pintype "bidirectional"))
    )
    (net (code "70") (name "unconnected-(GECKO-PadPE1)") (class "Default")
      (node (ref "GECKO") (pin "PE1") (pinfunction "PE1_PE1") (pintype "bidirectional"))
    )
    (net (code "71") (name "unconnected-(GECKO-PadPE2)") (class "Default")
      (node (ref "GECKO") (pin "PE2") (pinfunction "PE2_PE2") (pintype "bidirectional"))
    )
    (net (code "72") (name "unconnected-(GECKO-PadPE3)") (class "Default")
      (node (ref "GECKO") (pin "PE3") (pinfunction "PE3_PE3") (pintype "bidirectional"))
    )
    (net (code "73") (name "unconnected-(M1-AIO0-Pad30)") (class "Default")
      (node (ref "M1") (pin "30") (pinfunction "AIO0_30") (pintype "bidirectional"))
    )
    (net (code "74") (name "unconnected-(M1-AIO1-Pad35)") (class "Default")
      (node (ref "M1") (pin "35") (pinfunction "AIO1_35") (pintype "bidirectional"))
    )
    (net (code "75") (name "unconnected-(M1-GPIO3-Pad20)") (class "Default")
      (node (ref "M1") (pin "20") (pinfunction "GPIO3_20") (pintype "bidirectional"))
    )
    (net (code "76") (name "unconnected-(M1-GPIO4-Pad22)") (class "Default")
      (node (ref "M1") (pin "22") (pinfunction "GPIO4_22") (pintype "bidirectional"))
    )
    (net (code "77") (name "unconnected-(M1-GPIO6-Pad3)") (class "Default")
      (node (ref "M1") (pin "3") (pinfunction "GPIO6_3") (pintype "bidirectional"))
    )
    (net (code "78") (name "unconnected-(M1-GPIO9-Pad32)") (class "Default")
      (node (ref "M1") (pin "32") (pinfunction "GPIO9_32") (pintype "bidirectional"))
    )
    (net (code "79") (name "unconnected-(M1-GPIO10-Pad33)") (class "Default")
      (node (ref "M1") (pin "33") (pinfunction "GPIO10_33") (pintype "bidirectional"))
    )
    (net (code "80") (name "unconnected-(M1-GPIO11-Pad34)") (class "Default")
      (node (ref "M1") (pin "34") (pinfunction "GPIO11_34") (pintype "bidirectional"))
    )
    (net (code "81") (name "unconnected-(M1-PCM_CLOCK-Pad7)") (class "Default")
      (node (ref "M1") (pin "7") (pinfunction "PCM_CLOCK_7") (pintype "bidirectional"))
    )
    (net (code "82") (name "unconnected-(M1-PCM_IN-Pad9)") (class "Default")
      (node (ref "M1") (pin "9") (pinfunction "PCM_IN_9") (pintype "bidirectional"))
    )
    (net (code "83") (name "unconnected-(M1-PCM_OUT-Pad10)") (class "Default")
      (node (ref "M1") (pin "10") (pinfunction "PCM_OUT_10") (pintype "bidirectional"))
    )
    (net (code "84") (name "unconnected-(M1-PCM_SYNC-Pad8)") (class "Default")
      (node (ref "M1") (pin "8") (pinfunction "PCM_SYNC_8") (pintype "bidirectional"))
    )
    (net (code "85") (name "unconnected-(M1-SPI_CLOCK-Pad6)") (class "Default")
      (node (ref "M1") (pin "6") (pinfunction "SPI_CLOCK_6") (pintype "bidirectional"))
    )
    (net (code "86") (name "unconnected-(M1-SPI_CSB-Pad23)") (class "Default")
      (node (ref "M1") (pin "23") (pinfunction "SPI_CSB_23") (pintype "bidirectional"))
    )
    (net (code "87") (name "unconnected-(M1-SPI_MISO-Pad24)") (class "Default")
      (node (ref "M1") (pin "24") (pinfunction "SPI_MISO_24") (pintype "bidirectional"))
    )
    (net (code "88") (name "unconnected-(M1-SPI_MOSI-Pad2)") (class "Default")
      (node (ref "M1") (pin "2") (pinfunction "SPI_MOSI_2") (pintype "bidirectional"))
    )
    (net (code "89") (name "unconnected-(M1-UART_CTS-Pad16)") (class "Default")
      (node (ref "M1") (pin "16") (pinfunction "UART_CTS_16") (pintype "bidirectional"))
    )
    (net (code "90") (name "unconnected-(M1-UART_RTS-Pad15)") (class "Default")
      (node (ref "M1") (pin "15") (pinfunction "UART_RTS_15") (pintype "bidirectional"))
    )
    (net (code "91") (name "unconnected-(M1-USB_D+-Pad17)") (class "Default")
      (node (ref "M1") (pin "17") (pinfunction "USB_D+_17") (pintype "bidirectional"))
    )
    (net (code "92") (name "unconnected-(M1-USB_D--Pad18)") (class "Default")
      (node (ref "M1") (pin "18") (pinfunction "USB_D-_18") (pintype "bidirectional"))
    )
  )
)
